# Mounting.net
KiCad netlist of a schematic drawn in Altium Designer
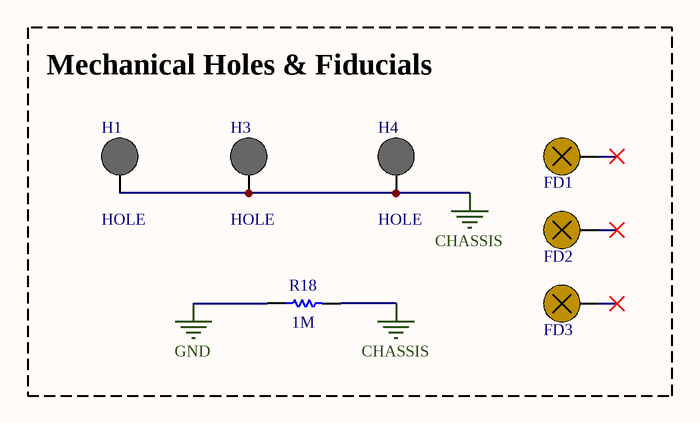
[diagram p0: Mounting.SchDoc]

(export (version "E")
  (design (tool "Eeschema 10.0.6"))
  (components
    (comp (ref "FD1") (value "FIDUCIAL") (footprint "FIDUCIAL") (libsource (lib "Library") (part "FIDUCIAL")))
    (comp (ref "FD2") (value "FIDUCIAL") (footprint "FIDUCIAL") (libsource (lib "Library") (part "FIDUCIAL")))
    (comp (ref "FD3") (value "FIDUCIAL") (footprint "FIDUCIAL") (libsource (lib "Library") (part "FIDUCIAL")))
    (comp (ref "H1") (value "HOLE") (footprint "HOLE_M3") (libsource (lib "ESP32 Platform") (part "HOLE")))
    (comp (ref "H3") (value "HOLE") (footprint "HOLE_M3") (libsource (lib "ESP32 Platform") (part "HOLE")))
    (comp (ref "H4") (value "HOLE") (footprint "HOLE_M3") (libsource (lib "ESP32 Platform") (part "HOLE")))
    (comp (ref "R18")
      (value "1M")
      (footprint "0805")
      (description "Resistencia SMD 470ohms")
      (fields
        (field (name "MANUFACTURER") "YAGEO")
        (field (name "MANUFACTURER PART NUMBER") "RC0805FR-071ML")
      )
      (libsource (lib "ESP32 Platform") (part "RES"))
    )
  )
  (nets
    (net (code "1") (name "CHASSIS") (class "Default")
      (node (ref "H1") (pin "1") (pinfunction "1_1") (pintype "passive"))
      (node (ref "H3") (pin "1") (pinfunction "1_1") (pintype "passive"))
      (node (ref "H4") (pin "1") (pinfunction "1_1") (pintype "passive"))
      (node (ref "R18") (pin "2") (pinfunction "2_2") (pintype "passive"))
    )
    (net (code "2") (name "GND") (class "Default")
      (node (ref "R18") (pin "1") (pinfunction "1_1") (pintype "passive"))
    )
    (net (code "3") (name "unconnected-(FD1-Pad1)") (class "Default")
      (node (ref "FD1") (pin "1") (pinfunction "1_1") (pintype "passive+no_connect"))
    )
    (net (code "4") (name "unconnected-(FD2-Pad1)") (class "Default")
      (node (ref "FD2") (pin "1") (pinfunction "1_1") (pintype "passive+no_connect"))
    )
    (net (code "5") (name "unconnected-(FD3-Pad1)") (class "Default")
      (node (ref "FD3") (pin "1") (pinfunction "1_1") (pintype "passive+no_connect"))
    )
  )
)
